# Urukul_FPGA_Supply.net
KiCad netlist of a schematic drawn in Altium Designer
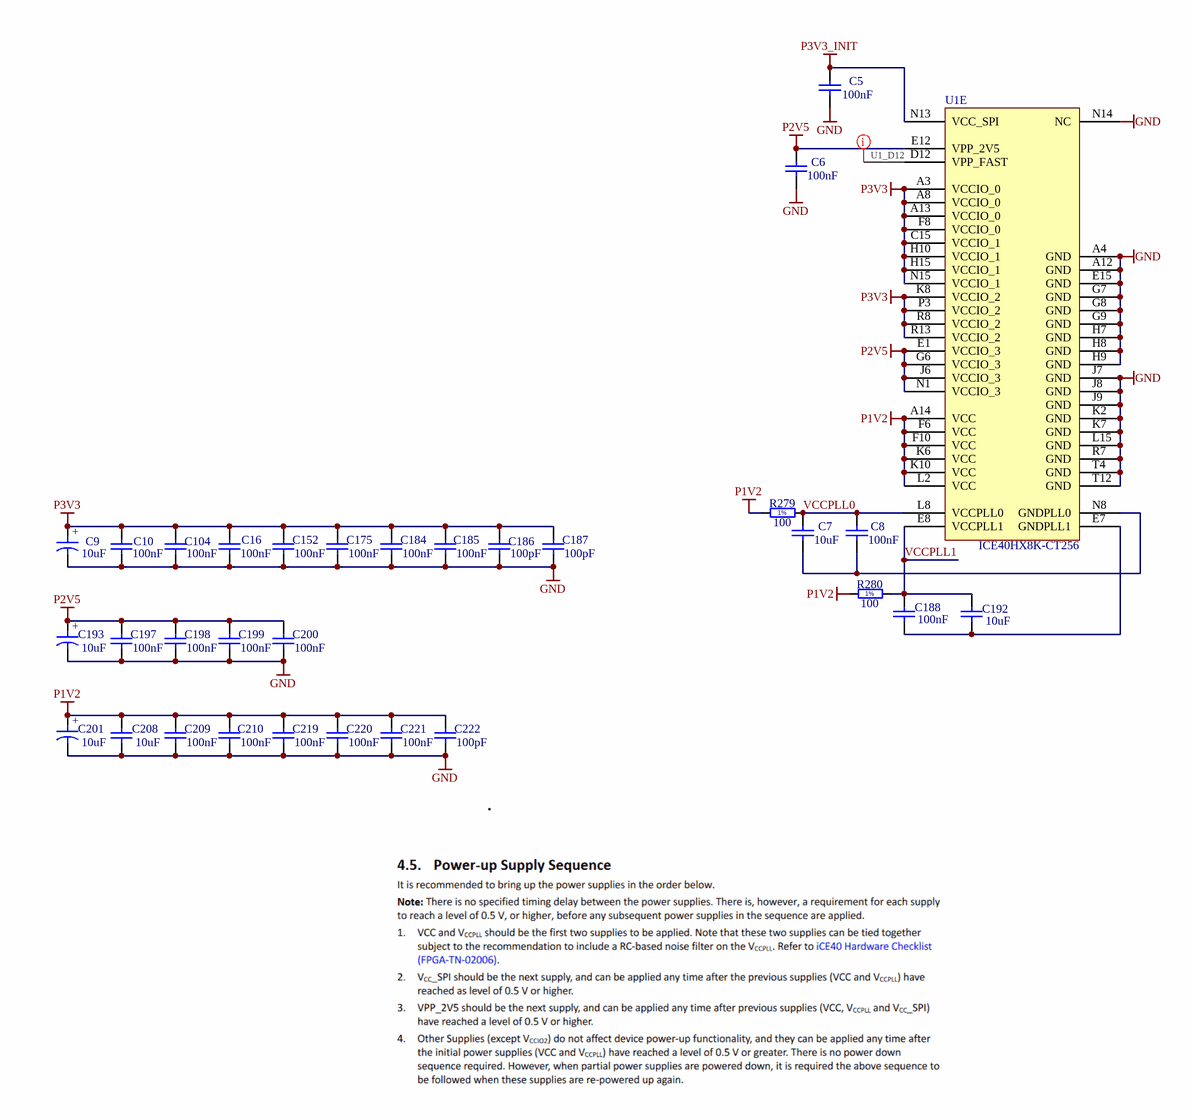
[diagram p0: Urukul_FPGA_Supply.SchDoc]

(export (version "E")
  (design (tool "Eeschema 10.0.6"))
  (components
    (comp (ref "C5")
      (value "100nF")
      (footprint "CAPC1005X55N")
      (description "Non-polarised capacitor")
      (fields
        (field (name "PART NUMBER") "CC0402_100NF_16V_10%_X5R")
        (field (name "VOLTAGE") "16V")
        (field (name "AUTHOR") "CERN DEM JLC")
      )
      (libsource (lib "Capacitors") (part "Capacitor - non polarized"))
    )
    (comp (ref "C6")
      (value "100nF")
      (footprint "CAPC1005X55N")
      (description "Non-polarised capacitor")
      (fields
        (field (name "PART NUMBER") "CC0402_100NF_16V_10%_X5R")
        (field (name "VOLTAGE") "16V")
        (field (name "AUTHOR") "CERN DEM JLC")
      )
      (libsource (lib "Capacitors") (part "Capacitor - non polarized"))
    )
    (comp (ref "C7")
      (value "10uF")
      (footprint "CAPC1005X70N")
      (description "Non-polarised capacitor")
      (fields
        (field (name "PART NUMBER") "CC0402_10UF_6.3V_20%_X5R")
        (field (name "VOLTAGE") "6.3V")
        (field (name "AUTHOR") "CERN DEM JLC")
      )
      (libsource (lib "Capacitors") (part "Capacitor - non polarized"))
    )
    (comp (ref "C8")
      (value "100nF")
      (footprint "CAPC1005X55N")
      (description "Non-polarised capacitor")
      (fields
        (field (name "PART NUMBER") "CC0402_100NF_16V_10%_X5R")
        (field (name "VOLTAGE") "16V")
        (field (name "AUTHOR") "CERN DEM JLC")
      )
      (libsource (lib "Capacitors") (part "Capacitor - non polarized"))
    )
    (comp (ref "C9")
      (value "10uF")
      (footprint "CAPMP3216X180N")
      (description "Polarised capacitor")
      (fields
        (field (name "PART NUMBER") "CTE3216-18_10UF_16V_20%_AVX_TCJ")
        (field (name "VOLTAGE") "16V")
        (field (name "AUTHOR") "CERN DEM JLC")
      )
      (libsource (lib "Capacitors") (part "Capacitor - polarized"))
    )
    (comp (ref "C10")
      (value "100nF")
      (footprint "CAPC1005X55N")
      (description "Non-polarised capacitor")
      (fields
        (field (name "PART NUMBER") "CC0402_100NF_16V_10%_X5R")
        (field (name "VOLTAGE") "16V")
        (field (name "AUTHOR") "CERN DEM JLC")
      )
      (libsource (lib "Capacitors") (part "Capacitor - non polarized"))
    )
    (comp (ref "C16")
      (value "100nF")
      (footprint "CAPC1005X55N")
      (description "Non-polarised capacitor")
      (fields
        (field (name "PART NUMBER") "CC0402_100NF_16V_10%_X5R")
        (field (name "VOLTAGE") "16V")
        (field (name "AUTHOR") "CERN DEM JLC")
      )
      (libsource (lib "Capacitors") (part "Capacitor - non polarized"))
    )
    (comp (ref "C104")
      (value "100nF")
      (footprint "CAPC1005X55N")
      (description "Non-polarised capacitor")
      (fields
        (field (name "PART NUMBER") "CC0402_100NF_16V_10%_X5R")
        (field (name "VOLTAGE") "16V")
        (field (name "AUTHOR") "CERN DEM JLC")
      )
      (libsource (lib "Capacitors") (part "Capacitor - non polarized"))
    )
    (comp (ref "C152")
      (value "100nF")
      (footprint "CAPC1005X55N")
      (description "Non-polarised capacitor")
      (fields
        (field (name "PART NUMBER") "CC0402_100NF_16V_10%_X5R")
        (field (name "VOLTAGE") "16V")
        (field (name "AUTHOR") "CERN DEM JLC")
      )
      (libsource (lib "Capacitors") (part "Capacitor - non polarized"))
    )
    (comp (ref "C175")
      (value "100nF")
      (footprint "CAPC1005X55N")
      (description "Non-polarised capacitor")
      (fields
        (field (name "PART NUMBER") "CC0402_100NF_16V_10%_X5R")
        (field (name "VOLTAGE") "16V")
        (field (name "AUTHOR") "CERN DEM JLC")
      )
      (libsource (lib "Capacitors") (part "Capacitor - non polarized"))
    )
    (comp (ref "C184")
      (value "100nF")
      (footprint "CAPC1005X55N")
      (description "Non-polarised capacitor")
      (fields
        (field (name "PART NUMBER") "CC0402_100NF_16V_10%_X5R")
        (field (name "VOLTAGE") "16V")
        (field (name "AUTHOR") "CERN DEM JLC")
      )
      (libsource (lib "Capacitors") (part "Capacitor - non polarized"))
    )
    (comp (ref "C185")
      (value "100nF")
      (footprint "CAPC1005X55N")
      (description "Non-polarised capacitor")
      (fields
        (field (name "PART NUMBER") "CC0402_100NF_16V_10%_X5R")
        (field (name "VOLTAGE") "16V")
        (field (name "AUTHOR") "CERN DEM JLC")
      )
      (libsource (lib "Capacitors") (part "Capacitor - non polarized"))
    )
    (comp (ref "C186")
      (value "100pF")
      (footprint "CAPC1005X55N")
      (description "Non-polarised capacitor")
      (fields
        (field (name "PART NUMBER") "CC0402_100PF_50V_5%_C0G")
        (field (name "VOLTAGE") "50V")
        (field (name "AUTHOR") "CERN DEM JLC")
      )
      (libsource (lib "Capacitors") (part "Capacitor - non polarized"))
    )
    (comp (ref "C187")
      (value "100pF")
      (footprint "CAPC1005X55N")
      (description "Non-polarised capacitor")
      (fields
        (field (name "PART NUMBER") "CC0402_100PF_50V_5%_C0G")
        (field (name "VOLTAGE") "50V")
        (field (name "AUTHOR") "CERN DEM JLC")
      )
      (libsource (lib "Capacitors") (part "Capacitor - non polarized"))
    )
    (comp (ref "C188")
      (value "100nF")
      (footprint "CAPC1005X55N")
      (description "Non-polarised capacitor")
      (fields
        (field (name "PART NUMBER") "CC0402_100NF_16V_10%_X5R")
        (field (name "VOLTAGE") "16V")
        (field (name "AUTHOR") "CERN DEM JLC")
      )
      (libsource (lib "Capacitors") (part "Capacitor - non polarized"))
    )
    (comp (ref "C192")
      (value "10uF")
      (footprint "CAPC1005X70N")
      (description "Non-polarised capacitor")
      (fields
        (field (name "PART NUMBER") "CC0402_10UF_6.3V_20%_X5R")
        (field (name "VOLTAGE") "6.3V")
        (field (name "AUTHOR") "CERN DEM JLC")
      )
      (libsource (lib "Capacitors") (part "Capacitor - non polarized"))
    )
    (comp (ref "C193")
      (value "10uF")
      (footprint "CAPMP3216X180N")
      (description "Polarised capacitor")
      (fields
        (field (name "PART NUMBER") "CTE3216-18_10UF_16V_20%_AVX_TCJ")
        (field (name "VOLTAGE") "16V")
        (field (name "AUTHOR") "CERN DEM JLC")
      )
      (libsource (lib "Capacitors") (part "Capacitor - polarized"))
    )
    (comp (ref "C197")
      (value "100nF")
      (footprint "CAPC1005X55N")
      (description "Non-polarised capacitor")
      (fields
        (field (name "PART NUMBER") "CC0402_100NF_16V_10%_X5R")
        (field (name "VOLTAGE") "16V")
        (field (name "AUTHOR") "CERN DEM JLC")
      )
      (libsource (lib "Capacitors") (part "Capacitor - non polarized"))
    )
    (comp (ref "C198")
      (value "100nF")
      (footprint "CAPC1005X55N")
      (description "Non-polarised capacitor")
      (fields
        (field (name "PART NUMBER") "CC0402_100NF_16V_10%_X5R")
        (field (name "VOLTAGE") "16V")
        (field (name "AUTHOR") "CERN DEM JLC")
      )
      (libsource (lib "Capacitors") (part "Capacitor - non polarized"))
    )
    (comp (ref "C199")
      (value "100nF")
      (footprint "CAPC1005X55N")
      (description "Non-polarised capacitor")
      (fields
        (field (name "PART NUMBER") "CC0402_100NF_16V_10%_X5R")
        (field (name "VOLTAGE") "16V")
        (field (name "AUTHOR") "CERN DEM JLC")
      )
      (libsource (lib "Capacitors") (part "Capacitor - non polarized"))
    )
    (comp (ref "C200")
      (value "100nF")
      (footprint "CAPC1005X55N")
      (description "Non-polarised capacitor")
      (fields
        (field (name "PART NUMBER") "CC0402_100NF_16V_10%_X5R")
        (field (name "VOLTAGE") "16V")
        (field (name "AUTHOR") "CERN DEM JLC")
      )
      (libsource (lib "Capacitors") (part "Capacitor - non polarized"))
    )
    (comp (ref "C201")
      (value "10uF")
      (footprint "CAPMP3216X180N")
      (description "Polarised capacitor")
      (fields
        (field (name "PART NUMBER") "CTE3216-18_10UF_16V_20%_AVX_TCJ")
        (field (name "VOLTAGE") "16V")
        (field (name "AUTHOR") "CERN DEM JLC")
      )
      (libsource (lib "Capacitors") (part "Capacitor - polarized"))
    )
    (comp (ref "C208")
      (value "10uF")
      (footprint "CAPC2012X135N")
      (description "Non-polarised capacitor")
      (fields
        (field (name "PART NUMBER") "CC0805_10UF_16V_10%_X5R")
        (field (name "VOLTAGE") "16V")
        (field (name "AUTHOR") "CERN DEM JLC")
      )
      (libsource (lib "Capacitors") (part "Capacitor - non polarized"))
    )
    (comp (ref "C209")
      (value "100nF")
      (footprint "CAPC1005X55N")
      (description "Non-polarised capacitor")
      (fields
        (field (name "PART NUMBER") "CC0402_100NF_16V_10%_X5R")
        (field (name "VOLTAGE") "16V")
        (field (name "AUTHOR") "CERN DEM JLC")
      )
      (libsource (lib "Capacitors") (part "Capacitor - non polarized"))
    )
    (comp (ref "C210")
      (value "100nF")
      (footprint "CAPC1005X55N")
      (description "Non-polarised capacitor")
      (fields
        (field (name "PART NUMBER") "CC0402_100NF_16V_10%_X5R")
        (field (name "VOLTAGE") "16V")
        (field (name "AUTHOR") "CERN DEM JLC")
      )
      (libsource (lib "Capacitors") (part "Capacitor - non polarized"))
    )
    (comp (ref "C219")
      (value "100nF")
      (footprint "CAPC1005X55N")
      (description "Non-polarised capacitor")
      (fields
        (field (name "PART NUMBER") "CC0402_100NF_16V_10%_X5R")
        (field (name "VOLTAGE") "16V")
        (field (name "AUTHOR") "CERN DEM JLC")
      )
      (libsource (lib "Capacitors") (part "Capacitor - non polarized"))
    )
    (comp (ref "C220")
      (value "100nF")
      (footprint "CAPC1005X55N")
      (description "Non-polarised capacitor")
      (fields
        (field (name "PART NUMBER") "CC0402_100NF_16V_10%_X5R")
        (field (name "VOLTAGE") "16V")
        (field (name "AUTHOR") "CERN DEM JLC")
      )
      (libsource (lib "Capacitors") (part "Capacitor - non polarized"))
    )
    (comp (ref "C221")
      (value "100nF")
      (footprint "CAPC1005X55N")
      (description "Non-polarised capacitor")
      (fields
        (field (name "PART NUMBER") "CC0402_100NF_16V_10%_X5R")
        (field (name "VOLTAGE") "16V")
        (field (name "AUTHOR") "CERN DEM JLC")
      )
      (libsource (lib "Capacitors") (part "Capacitor - non polarized"))
    )
    (comp (ref "C222")
      (value "100pF")
      (footprint "CAPC1005X55N")
      (description "Non-polarised capacitor")
      (fields
        (field (name "PART NUMBER") "CC0402_100PF_50V_5%_C0G")
        (field (name "VOLTAGE") "50V")
        (field (name "AUTHOR") "CERN DEM JLC")
      )
      (libsource (lib "Capacitors") (part "Capacitor - non polarized"))
    )
    (comp (ref "R279")
      (value "100")
      (footprint "RESC1005X40N")
      (description "Resistor - 1%")
      (fields
        (field (name "PART NUMBER") "R0402_100R_1%_0.0625W_100PPM")
        (field (name "POWER") "0.0625W")
        (field (name "AUTHOR") "CERN DEM JLC")
      )
      (libsource (lib "Resistors") (part "Resistor - 1%"))
    )
    (comp (ref "R280")
      (value "100")
      (footprint "RESC1005X40N")
      (description "Resistor - 1%")
      (fields
        (field (name "PART NUMBER") "R0402_100R_1%_0.0625W_100PPM")
        (field (name "POWER") "0.0625W")
        (field (name "AUTHOR") "CERN DEM JLC")
      )
      (libsource (lib "Resistors") (part "Resistor - 1%"))
    )
    (comp (ref "U1")
      (value "ICE40HX8K-CT256")
      (footprint "LATC-caBGA-256")
      (fields (field (name "MANUFACTURER") "Lattice Semiconductor"))
      (libsource (lib "Altium Content Vault") (part "LATC-HX8K-caBGA-256"))
    )
  )
  (nets
    (net (code "1") (name "/U1_D12") (class "Default")
      (node (ref "U1") (pin "D12") (pinfunction "VPP_FAST_D12") (pintype "power_in"))
    )
    (net (code "2") (name "/VCCPLL0") (class "Default")
      (node (ref "C7") (pin "2") (pinfunction "2_2") (pintype "passive"))
      (node (ref "C8") (pin "2") (pinfunction "2_2") (pintype "passive"))
      (node (ref "R279") (pin "2") (pinfunction "2_2") (pintype "passive"))
      (node (ref "U1") (pin "L8") (pinfunction "VCCPLL0_L8") (pintype "power_in"))
    )
    (net (code "3") (name "/VCCPLL1") (class "Default")
      (node (ref "C188") (pin "2") (pinfunction "2_2") (pintype "passive"))
      (node (ref "C192") (pin "2") (pinfunction "2_2") (pintype "passive"))
      (node (ref "R280") (pin "2") (pinfunction "2_2") (pintype "passive"))
      (node (ref "U1") (pin "E8") (pinfunction "VCCPLL1_E8") (pintype "power_in"))
    )
    (net (code "4") (name "GND") (class "Default")
      (node (ref "C10") (pin "1") (pinfunction "1_1") (pintype "passive"))
      (node (ref "C104") (pin "1") (pinfunction "1_1") (pintype "passive"))
      (node (ref "C152") (pin "1") (pinfunction "1_1") (pintype "passive"))
      (node (ref "C16") (pin "1") (pinfunction "1_1") (pintype "passive"))
      (node (ref "C175") (pin "1") (pinfunction "1_1") (pintype "passive"))
      (node (ref "C184") (pin "1") (pinfunction "1_1") (pintype "passive"))
      (node (ref "C185") (pin "1") (pinfunction "1_1") (pintype "passive"))
      (node (ref "C186") (pin "1") (pinfunction "1_1") (pintype "passive"))
      (node (ref "C187") (pin "1") (pinfunction "1_1") (pintype "passive"))
      (node (ref "C193") (pin "2") (pinfunction "2_2") (pintype "passive"))
      (node (ref "C197") (pin "1") (pinfunction "1_1") (pintype "passive"))
      (node (ref "C198") (pin "1") (pinfunction "1_1") (pintype "passive"))
      (node (ref "C199") (pin "1") (pinfunction "1_1") (pintype "passive"))
      (node (ref "C200") (pin "1") (pinfunction "1_1") (pintype "passive"))
      (node (ref "C201") (pin "2") (pinfunction "2_2") (pintype "passive"))
      (node (ref "C208") (pin "1") (pinfunction "1_1") (pintype "passive"))
      (node (ref "C209") (pin "1") (pinfunction "1_1") (pintype "passive"))
      (node (ref "C210") (pin "1") (pinfunction "1_1") (pintype "passive"))
      (node (ref "C219") (pin "1") (pinfunction "1_1") (pintype "passive"))
      (node (ref "C220") (pin "1") (pinfunction "1_1") (pintype "passive"))
      (node (ref "C221") (pin "1") (pinfunction "1_1") (pintype "passive"))
      (node (ref "C222") (pin "1") (pinfunction "1_1") (pintype "passive"))
      (node (ref "C5") (pin "1") (pinfunction "1_1") (pintype "passive"))
      (node (ref "C6") (pin "1") (pinfunction "1_1") (pintype "passive"))
      (node (ref "C9") (pin "2") (pinfunction "2_2") (pintype "passive"))
      (node (ref "U1") (pin "A12") (pinfunction "GND_A12") (pintype "power_in"))
      (node (ref "U1") (pin "A4") (pinfunction "GND_A4") (pintype "power_in"))
      (node (ref "U1") (pin "E15") (pinfunction "GND_E15") (pintype "power_in"))
      (node (ref "U1") (pin "G7") (pinfunction "GND_G7") (pintype "power_in"))
      (node (ref "U1") (pin "G8") (pinfunction "GND_G8") (pintype "power_in"))
      (node (ref "U1") (pin "G9") (pinfunction "GND_G9") (pintype "power_in"))
      (node (ref "U1") (pin "H7") (pinfunction "GND_H7") (pintype "power_in"))
      (node (ref "U1") (pin "H8") (pinfunction "GND_H8") (pintype "power_in"))
      (node (ref "U1") (pin "H9") (pinfunction "GND_H9") (pintype "power_in"))
      (node (ref "U1") (pin "J7") (pinfunction "GND_J7") (pintype "power_in"))
      (node (ref "U1") (pin "J8") (pinfunction "GND_J8") (pintype "power_in"))
      (node (ref "U1") (pin "J9") (pinfunction "GND_J9") (pintype "power_in"))
      (node (ref "U1") (pin "K2") (pinfunction "GND_K2") (pintype "power_in"))
      (node (ref "U1") (pin "K7") (pinfunction "GND_K7") (pintype "power_in"))
      (node (ref "U1") (pin "L15") (pinfunction "GND_L15") (pintype "power_in"))
      (node (ref "U1") (pin "N14") (pinfunction "NC_N14") (pintype "passive"))
      (node (ref "U1") (pin "R7") (pinfunction "GND_R7") (pintype "power_in"))
      (node (ref "U1") (pin "T12") (pinfunction "GND_T12") (pintype "power_in"))
      (node (ref "U1") (pin "T4") (pinfunction "GND_T4") (pintype "power_in"))
    )
    (net (code "5") (name "Net-(U1E-GNDPLL0)") (class "Default")
      (node (ref "C7") (pin "1") (pinfunction "1_1") (pintype "passive"))
      (node (ref "C8") (pin "1") (pinfunction "1_1") (pintype "passive"))
      (node (ref "U1") (pin "N8") (pinfunction "GNDPLL0_N8") (pintype "power_in"))
    )
    (net (code "6") (name "Net-(U1E-GNDPLL1)") (class "Default")
      (node (ref "C188") (pin "1") (pinfunction "1_1") (pintype "passive"))
      (node (ref "C192") (pin "1") (pinfunction "1_1") (pintype "passive"))
      (node (ref "U1") (pin "E7") (pinfunction "GNDPLL1_E7") (pintype "power_in"))
    )
    (net (code "7") (name "P1V2") (class "Default")
      (node (ref "C201") (pin "1") (pinfunction "1_1") (pintype "passive"))
      (node (ref "C208") (pin "2") (pinfunction "2_2") (pintype "passive"))
      (node (ref "C209") (pin "2") (pinfunction "2_2") (pintype "passive"))
      (node (ref "C210") (pin "2") (pinfunction "2_2") (pintype "passive"))
      (node (ref "C219") (pin "2") (pinfunction "2_2") (pintype "passive"))
      (node (ref "C220") (pin "2") (pinfunction "2_2") (pintype "passive"))
      (node (ref "C221") (pin "2") (pinfunction "2_2") (pintype "passive"))
      (node (ref "C222") (pin "2") (pinfunction "2_2") (pintype "passive"))
      (node (ref "R279") (pin "1") (pinfunction "1_1") (pintype "passive"))
      (node (ref "R280") (pin "1") (pinfunction "1_1") (pintype "passive"))
      (node (ref "U1") (pin "A14") (pinfunction "VCC_A14") (pintype "power_in"))
      (node (ref "U1") (pin "F10") (pinfunction "VCC_F10") (pintype "power_in"))
      (node (ref "U1") (pin "F6") (pinfunction "VCC_F6") (pintype "power_in"))
      (node (ref "U1") (pin "K10") (pinfunction "VCC_K10") (pintype "power_in"))
      (node (ref "U1") (pin "K6") (pinfunction "VCC_K6") (pintype "power_in"))
      (node (ref "U1") (pin "L2") (pinfunction "VCC_L2") (pintype "power_in"))
    )
    (net (code "8") (name "P2V5") (class "Default")
      (node (ref "C193") (pin "1") (pinfunction "1_1") (pintype "passive"))
      (node (ref "C197") (pin "2") (pinfunction "2_2") (pintype "passive"))
      (node (ref "C198") (pin "2") (pinfunction "2_2") (pintype "passive"))
      (node (ref "C199") (pin "2") (pinfunction "2_2") (pintype "passive"))
      (node (ref "C200") (pin "2") (pinfunction "2_2") (pintype "passive"))
      (node (ref "C6") (pin "2") (pinfunction "2_2") (pintype "passive"))
      (node (ref "U1") (pin "E1") (pinfunction "VCCIO_3_E1") (pintype "power_in"))
      (node (ref "U1") (pin "E12") (pinfunction "VPP_2V5_E12") (pintype "power_in"))
      (node (ref "U1") (pin "G6") (pinfunction "VCCIO_3_G6") (pintype "power_in"))
      (node (ref "U1") (pin "J6") (pinfunction "VCCIO_3_J6") (pintype "power_in"))
      (node (ref "U1") (pin "N1") (pinfunction "VCCIO_3_N1") (pintype "power_in"))
    )
    (net (code "9") (name "P3V3") (class "Default")
      (node (ref "C10") (pin "2") (pinfunction "2_2") (pintype "passive"))
      (node (ref "C104") (pin "2") (pinfunction "2_2") (pintype "passive"))
      (node (ref "C152") (pin "2") (pinfunction "2_2") (pintype "passive"))
      (node (ref "C16") (pin "2") (pinfunction "2_2") (pintype "passive"))
      (node (ref "C175") (pin "2") (pinfunction "2_2") (pintype "passive"))
      (node (ref "C184") (pin "2") (pinfunction "2_2") (pintype "passive"))
      (node (ref "C185") (pin "2") (pinfunction "2_2") (pintype "passive"))
      (node (ref "C186") (pin "2") (pinfunction "2_2") (pintype "passive"))
      (node (ref "C187") (pin "2") (pinfunction "2_2") (pintype "passive"))
      (node (ref "C9") (pin "1") (pinfunction "1_1") (pintype "passive"))
      (node (ref "U1") (pin "A13") (pinfunction "VCCIO_0_A13") (pintype "power_in"))
      (node (ref "U1") (pin "A3") (pinfunction "VCCIO_0_A3") (pintype "power_in"))
      (node (ref "U1") (pin "A8") (pinfunction "VCCIO_0_A8") (pintype "power_in"))
      (node (ref "U1") (pin "C15") (pinfunction "VCCIO_1_C15") (pintype "power_in"))
      (node (ref "U1") (pin "F8") (pinfunction "VCCIO_0_F8") (pintype "power_in"))
      (node (ref "U1") (pin "H10") (pinfunction "VCCIO_1_H10") (pintype "power_in"))
      (node (ref "U1") (pin "H15") (pinfunction "VCCIO_1_H15") (pintype "power_in"))
      (node (ref "U1") (pin "K8") (pinfunction "VCCIO_2_K8") (pintype "power_in"))
      (node (ref "U1") (pin "N15") (pinfunction "VCCIO_1_N15") (pintype "power_in"))
      (node (ref "U1") (pin "P3") (pinfunction "VCCIO_2_P3") (pintype "power_in"))
      (node (ref "U1") (pin "R13") (pinfunction "VCCIO_2_R13") (pintype "power_in"))
      (node (ref "U1") (pin "R8") (pinfunction "VCCIO_2_R8") (pintype "power_in"))
    )
    (net (code "10") (name "P3V3_INIT") (class "Default")
      (node (ref "C5") (pin "2") (pinfunction "2_2") (pintype "passive"))
      (node (ref "U1") (pin "N13") (pinfunction "VCC_SPI_N13") (pintype "power_in"))
    )
  )
)
